# 11-NCP3063_LCD.net
KiCad netlist of a schematic drawn in Altium Designer
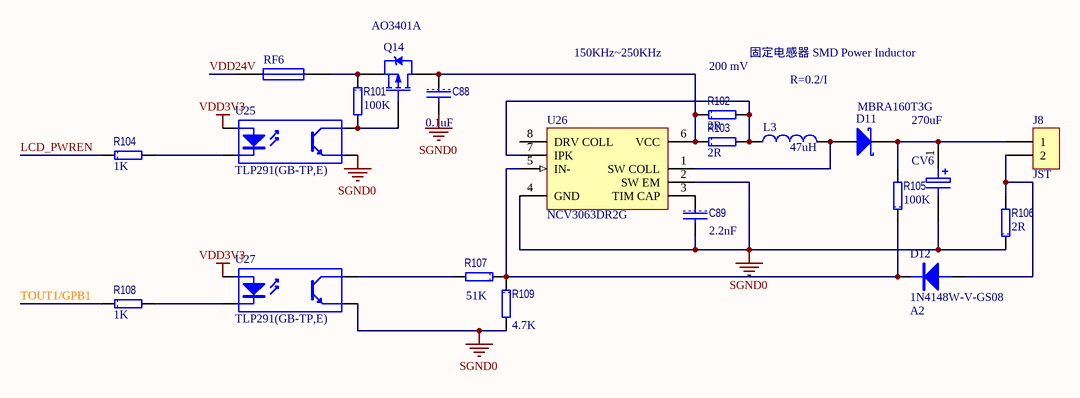
[diagram p0: 11-NCP3063_LCD背光.SchDoc]

(export (version "E")
  (design (tool "Eeschema 10.0.6"))
  (components
    (comp (ref "C88")
      (value "0.1uF")
      (footprint "1608[0603]C")
      (description "多层陶瓷电容器MLCC - SMD/SMT 0603 0.1uF 50volts X7R 10%")
      (fields (field (name "MANUFACTURER") "TDK") (field (name "MANUFACTURER PART NUMBER") "C1608X7R1H104K"))
      (libsource (lib "*") (part "CAP"))
    )
    (comp (ref "C89")
      (value "2.2nF")
      (footprint "1608[0603]C")
      (description "多层陶瓷电容器MLCC - SMD/SMT 0603 2200pF 50volts X7R 10%")
      (fields (field (name "MANUFACTURER") "TDK") (field (name "MANUFACTURER PART NUMBER") "C1608X7R1H222K"))
      (libsource (lib "*") (part "CAP"))
    )
    (comp (ref "CV6")
      (value "270uF")
      (footprint "CAPPR5-10x20/H1.1")
      (description "插针 铝质电解电容器 - 带引线 270UF 50V ELECT FM RADIAL")
      (fields
        (field (name "MANUFACTURER") "Panasonic Electronic Components")
        (field (name "MANUFACTURER PART NUMBER") "EEU-FM1H271")
      )
      (libsource (lib "*") (part "ELECTRO1"))
    )
    (comp (ref "D11")
      (value "MBRA160T3G")
      (footprint "DO-214AC/SMA")
      (description "肖特基二极管与整流器 60 Volt 1.0 A")
      (fields (field (name "MANUFACTURER") "ON Semiconductor"))
      (libsource (lib "IR Rectifier - Schottky") (part "10BQ060"))
    )
    (comp (ref "D12")
      (value "1N4148W-V-GS08")
      (footprint "SOD323")
      (description "二极管 - 通用，功率，开关 100V Io/150mA")
      (fields (field (name "MANUFACTURER") "Vishay Semiconductors") (field (name "ALTIUM_VALUE") "A2"))
      (libsource (lib "IN4148") (part "1N4148W"))
    )
    (comp (ref "J8") (value "JST") (footprint "JST") (description "CON") (libsource (lib "*") (part "CON2")))
    (comp (ref "L3")
      (value "47uH")
      (footprint "INDP5050X28N")
      (description "固定电感器 SMD Power Inductor")
      (fields
        (field (name "MANUFACTURER") "Sumida")
        (field (name "MANUFACTURER PART NUMBER") "CDRH5D28RH125NP-470MC")
        (field (name "DESCRIPTION 1") "固定电感器 SMD Power Inductor")
      )
      (libsource (lib "Miscellaneous Devices") (part "Inductor"))
    )
    (comp (ref "Q14")
      (value "AO3401A")
      (footprint "SOT23_N")
      (description "MOSFET P-CH -30V -4.3A SOT23")
      (fields (field (name "MANUFACTURER") "Alpha & Omega Semiconductor Inc"))
      (libsource (lib "IR Discrete MOSFET - Power") (part "IRLML5103"))
    )
    (comp (ref "R101")
      (value "100K")
      (footprint "1608[0603]R")
      (description "厚膜电阻器 - SMD 1/10watt 100Kohms 1%")
      (fields
        (field (name "MANUFACTURER") "Vishay / Dale")
        (field (name "MANUFACTURER PART NUMBER") "CRCW0603100KFKEA")
      )
      (libsource (lib "100K 1%") (part "RES"))
    )
    (comp (ref "R102")
      (value "2R")
      (footprint "1608[0603]R")
      (description "厚膜电阻器 - SMD 1/10watt 2ohms 1%")
      (fields
        (field (name "MANUFACTURER") "Vishay / Dale")
        (field (name "MANUFACTURER PART NUMBER") "CRCW06032R00FKEA")
      )
      (libsource (lib "2R 1%") (part "RES"))
    )
    (comp (ref "R103")
      (value "2R")
      (footprint "1608[0603]R")
      (description "厚膜电阻器 - SMD 1/10watt 2ohms 1%")
      (fields
        (field (name "MANUFACTURER") "Vishay / Dale")
        (field (name "MANUFACTURER PART NUMBER") "CRCW06032R00FKEA")
      )
      (libsource (lib "2R 1%") (part "RES"))
    )
    (comp (ref "R104")
      (value "1K")
      (footprint "1608[0603]R")
      (description "厚膜电阻器 - SMD 1/10watt 1.0Kohms 1%")
      (fields
        (field (name "MANUFACTURER") "Vishay / Dale")
        (field (name "MANUFACTURER PART NUMBER") "CRCW06031K00FKEA")
      )
      (libsource (lib "1K 1%") (part "RES"))
    )
    (comp (ref "R105")
      (value "100K")
      (footprint "1608[0603]R")
      (description "厚膜电阻器 - SMD 1/10watt 100Kohms 1%")
      (fields
        (field (name "MANUFACTURER") "Vishay / Dale")
        (field (name "MANUFACTURER PART NUMBER") "CRCW0603100KFKEA")
      )
      (libsource (lib "100K 1%") (part "RES"))
    )
    (comp (ref "R106")
      (value "2R")
      (footprint "1608[0603]R")
      (description "厚膜电阻器 - SMD 1/10watt 2ohms 1%")
      (fields
        (field (name "MANUFACTURER") "Vishay / Dale")
        (field (name "MANUFACTURER PART NUMBER") "CRCW06032R00FKEA")
      )
      (libsource (lib "2R 1%") (part "RES"))
    )
    (comp (ref "R107")
      (value "51K")
      (footprint "1608[0603]R")
      (description "厚膜电阻器 - SMD 1/10watt 51Kohms 1%")
      (fields
        (field (name "MANUFACTURER") "Vishay / Dale")
        (field (name "MANUFACTURER PART NUMBER") "CRCW060351K0FKEA")
      )
      (libsource (lib "10K 1%") (part "RES"))
    )
    (comp (ref "R108")
      (value "1K")
      (footprint "1608[0603]R")
      (description "厚膜电阻器 - SMD 1/10watt 1.0Kohms 1%")
      (fields
        (field (name "MANUFACTURER") "Vishay / Dale")
        (field (name "MANUFACTURER PART NUMBER") "CRCW06031K00FKEA")
      )
      (libsource (lib "1K 1%") (part "RES"))
    )
    (comp (ref "R109")
      (value "4.7K")
      (footprint "1608[0603]R")
      (description "厚膜电阻器 - SMD 1/10watt 4.7Kohms 1%")
      (fields
        (field (name "MANUFACTURER") "Vishay / Dale")
        (field (name "MANUFACTURER PART NUMBER") "CRCW06034K70FKEA")
      )
      (libsource (lib "10K 1%") (part "RES"))
    )
    (comp (ref "RF6")
      (value "1206L016WR")
      (footprint "3216[1206]")
      (description "可复位保险丝 PTC 30V POLY SURF MOUNT 1206 .160A")
      (fields (field (name "MANUFACTURER") "LITTELFUSE"))
      (libsource (lib "*") (part "FUSE1"))
    )
    (comp (ref "U25")
      (value "TLP291(GB-TP,E)")
      (footprint "SSOP4_N")
      (description "晶体管输出光电耦合器 80Vceo 2500Vrms standard")
      (fields
        (field (name "MANUFACTURER") "Toshiba")
        (field (name "MANUFACTURER PART NUMBER") "TLP281(GB-TP,F)")
      )
      (libsource (lib "Miscellaneous Devices") (part "Optoisolator1"))
    )
    (comp (ref "U26")
      (value "NCV3063DR2G")
      (footprint "SOIC8_N")
      (description "直流/直流开关转换器 1.5 A DCDC SW REG")
      (fields (field (name "MANUFACTURER") "ON Semiconductor"))
      (libsource (lib "ON Semi Power Mgt DC-DC Converter") (part "MC33063AD"))
    )
    (comp (ref "U27")
      (value "TLP291(GB-TP,E)")
      (footprint "SSOP4_N")
      (description "晶体管输出光电耦合器 80Vceo 2500Vrms standard")
      (fields
        (field (name "MANUFACTURER") "Toshiba")
        (field (name "MANUFACTURER PART NUMBER") "TLP281(GB-TP,F)")
      )
      (libsource (lib "Miscellaneous Devices") (part "Optoisolator1"))
    )
  )
  (nets
    (net (code "1") (name "/LCD_PWREN") (class "Default")
      (node (ref "R104") (pin "1") (pinfunction "1_1") (pintype "passive"))
    )
    (net (code "2") (name "/TOUT1{slash}GPB1") (class "Default")
      (node (ref "R108") (pin "1") (pinfunction "1_1") (pintype "passive"))
    )
    (net (code "3") (name "/VDD24V") (class "Default")
      (node (ref "RF6") (pin "1") (pinfunction "1_1") (pintype "passive"))
    )
    (net (code "4") (name "Net-(D11-A)") (class "Default")
      (node (ref "D11") (pin "1") (pinfunction "A_1") (pintype "passive"))
      (node (ref "L3") (pin "2") (pinfunction "2_2") (pintype "passive"))
      (node (ref "U26") (pin "1") (pinfunction "SW_COLL_1") (pintype "passive"))
    )
    (net (code "5") (name "Net-(D11-K)") (class "Default")
      (node (ref "CV6") (pin "1") (pinfunction "1_1") (pintype "passive"))
      (node (ref "D11") (pin "2") (pinfunction "K_2") (pintype "passive"))
      (node (ref "J8") (pin "1") (pinfunction "1_1") (pintype "passive"))
      (node (ref "R105") (pin "2") (pinfunction "2_2") (pintype "passive"))
    )
    (net (code "6") (name "Net-(D12-A)") (class "Default")
      (node (ref "D12") (pin "1") (pinfunction "A_1") (pintype "passive"))
      (node (ref "J8") (pin "2") (pinfunction "2_2") (pintype "passive"))
      (node (ref "R106") (pin "2") (pinfunction "2_2") (pintype "passive"))
    )
    (net (code "7") (name "Net-(D12-K)") (class "Default")
      (node (ref "D12") (pin "2") (pinfunction "K_2") (pintype "passive"))
      (node (ref "R105") (pin "1") (pinfunction "1_1") (pintype "passive"))
      (node (ref "R107") (pin "1") (pinfunction "1_1") (pintype "passive"))
      (node (ref "R109") (pin "1") (pinfunction "1_1") (pintype "passive"))
      (node (ref "U26") (pin "5") (pinfunction "IN-_5") (pintype "input"))
    )
    (net (code "8") (name "Net-(Q14-D)") (class "Default")
      (node (ref "C88") (pin "1") (pinfunction "1_1") (pintype "passive"))
      (node (ref "Q14") (pin "3") (pinfunction "D_3") (pintype "passive"))
      (node (ref "R102") (pin "1") (pinfunction "1_1") (pintype "passive"))
      (node (ref "R103") (pin "1") (pinfunction "1_1") (pintype "passive"))
      (node (ref "U26") (pin "6") (pinfunction "VCC_6") (pintype "power_in"))
    )
    (net (code "9") (name "Net-(Q14-G)") (class "Default")
      (node (ref "Q14") (pin "1") (pinfunction "G_1") (pintype "passive"))
      (node (ref "R101") (pin "2") (pinfunction "2_2") (pintype "passive"))
      (node (ref "U25") (pin "4") (pinfunction "C_4") (pintype "passive"))
    )
    (net (code "10") (name "Net-(Q14-S)") (class "Default")
      (node (ref "Q14") (pin "2") (pinfunction "S_2") (pintype "passive"))
      (node (ref "R101") (pin "1") (pinfunction "1_1") (pintype "passive"))
      (node (ref "RF6") (pin "2") (pinfunction "2_2") (pintype "passive"))
    )
    (net (code "11") (name "Net-(U25-K)") (class "Default")
      (node (ref "R104") (pin "2") (pinfunction "2_2") (pintype "passive"))
      (node (ref "U25") (pin "2") (pinfunction "K_2") (pintype "passive"))
    )
    (net (code "12") (name "Net-(U26-IPK)") (class "Default")
      (node (ref "L3") (pin "1") (pinfunction "1_1") (pintype "passive"))
      (node (ref "R102") (pin "2") (pinfunction "2_2") (pintype "passive"))
      (node (ref "R103") (pin "2") (pinfunction "2_2") (pintype "passive"))
      (node (ref "U26") (pin "7") (pinfunction "IPK_7") (pintype "passive"))
    )
    (net (code "13") (name "Net-(U26-TIM_CAP)") (class "Default")
      (node (ref "C89") (pin "1") (pinfunction "1_1") (pintype "passive"))
      (node (ref "U26") (pin "3") (pinfunction "TIM_CAP_3") (pintype "passive"))
    )
    (net (code "14") (name "Net-(U27-C)") (class "Default")
      (node (ref "R107") (pin "2") (pinfunction "2_2") (pintype "passive"))
      (node (ref "U27") (pin "4") (pinfunction "C_4") (pintype "passive"))
    )
    (net (code "15") (name "Net-(U27-K)") (class "Default")
      (node (ref "R108") (pin "2") (pinfunction "2_2") (pintype "passive"))
      (node (ref "U27") (pin "2") (pinfunction "K_2") (pintype "passive"))
    )
    (net (code "16") (name "SGND0") (class "Default")
      (node (ref "C88") (pin "2") (pinfunction "2_2") (pintype "passive"))
      (node (ref "C89") (pin "2") (pinfunction "2_2") (pintype "passive"))
      (node (ref "CV6") (pin "2") (pinfunction "2_2") (pintype "passive"))
      (node (ref "R106") (pin "1") (pinfunction "1_1") (pintype "passive"))
      (node (ref "R109") (pin "2") (pinfunction "2_2") (pintype "passive"))
      (node (ref "U25") (pin "3") (pinfunction "E_3") (pintype "passive"))
      (node (ref "U26") (pin "2") (pinfunction "SW_EM_2") (pintype "passive"))
      (node (ref "U26") (pin "4") (pinfunction "GND_4") (pintype "power_in"))
      (node (ref "U27") (pin "3") (pinfunction "E_3") (pintype "passive"))
    )
    (net (code "17") (name "VDD3V3") (class "Default")
      (node (ref "U25") (pin "1") (pinfunction "A_1") (pintype "passive"))
      (node (ref "U27") (pin "1") (pinfunction "A_1") (pintype "passive"))
    )
    (net (code "18") (name "unconnected-(U26-DRV_COLL-Pad8)") (class "Default")
      (node (ref "U26") (pin "8") (pinfunction "DRV_COLL_8") (pintype "open_collector"))
    )
  )
)
